# usb-shock-buzzer.net
KiCad netlist of a schematic drawn in EAGLE
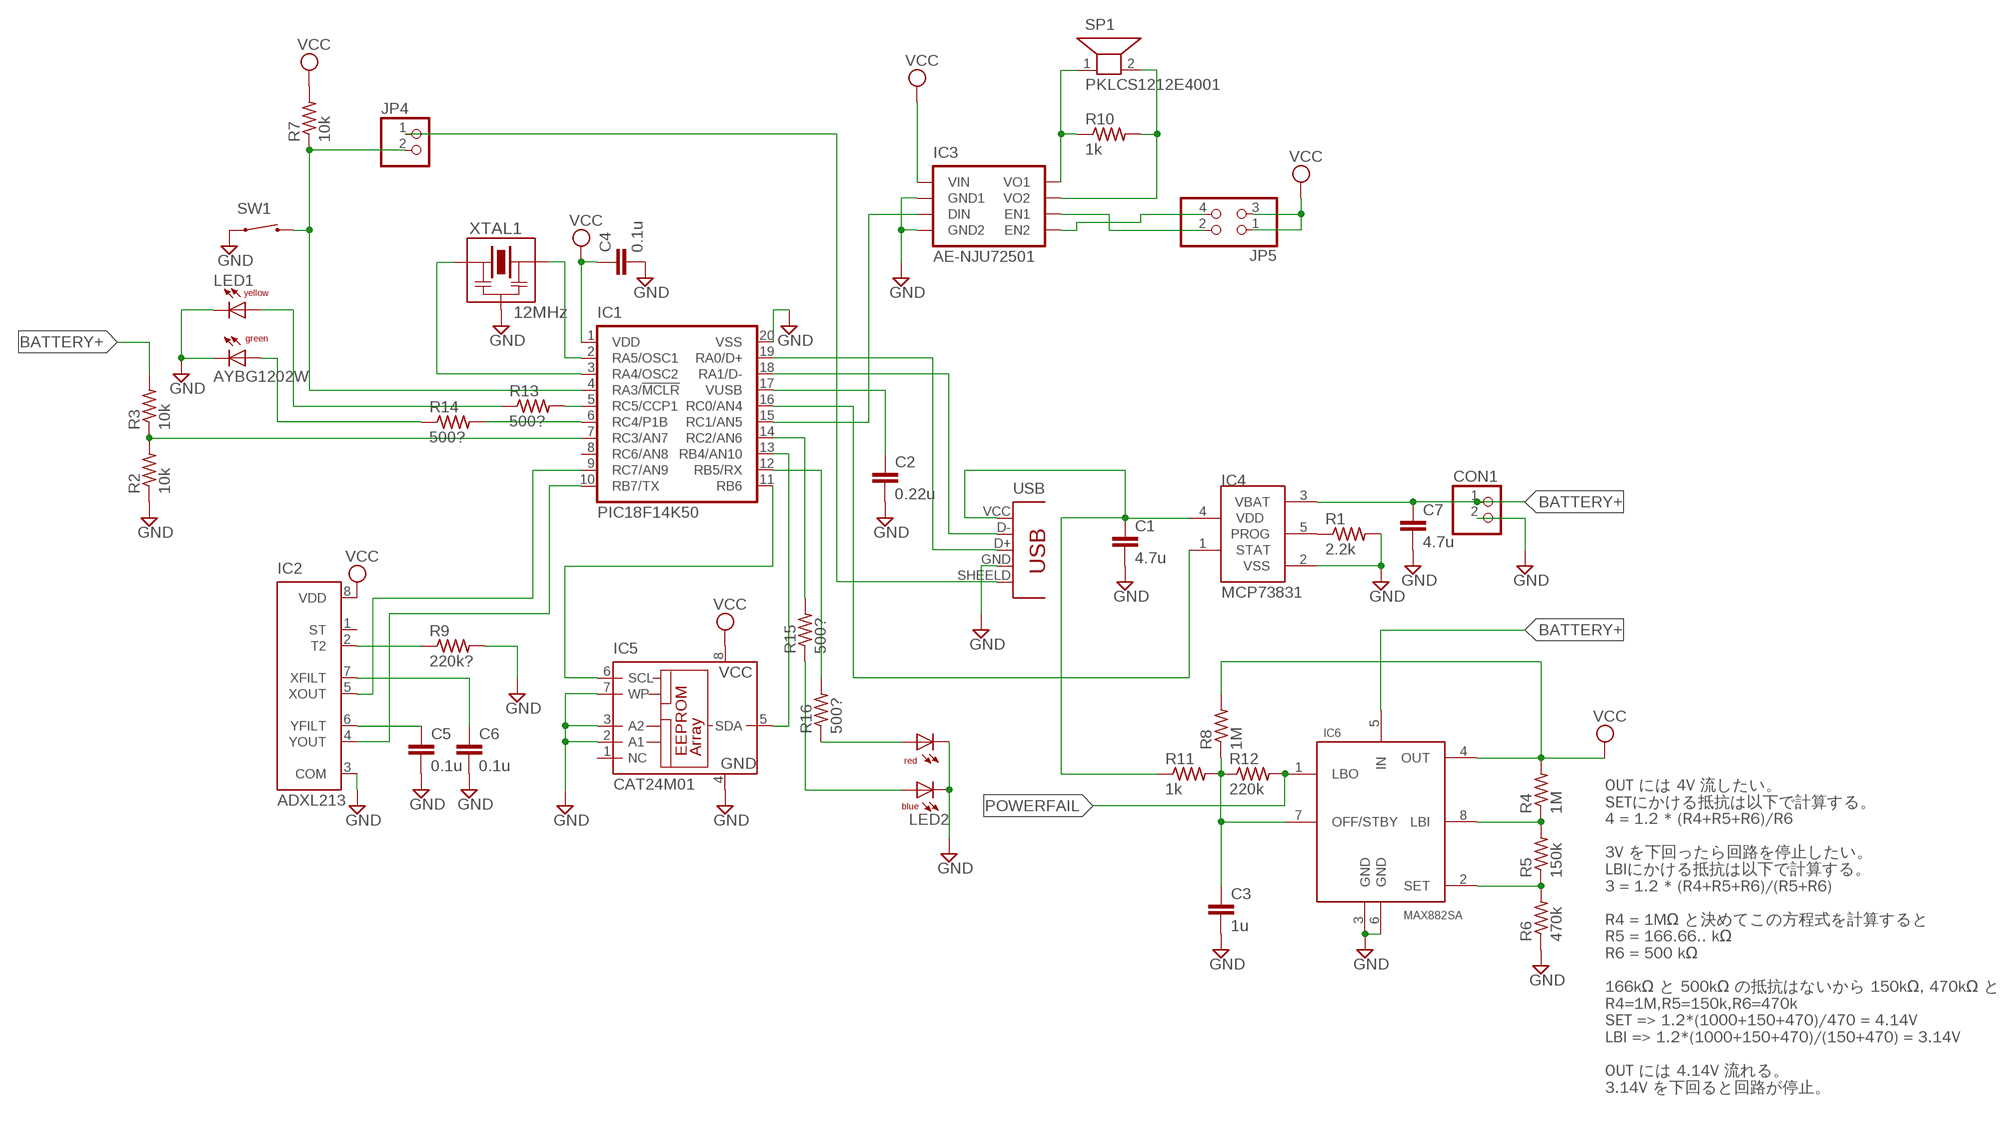
[diagram p0: schematic, sheet 1]

(export (version "E")
  (design (tool "Eeschema 10.0.6"))
  (components
    (comp (ref "C1")
      (value "4.7u")
      (footprint "eagle-import:C0805")
      (libsource (lib "eagle-import") (part "C-EUC0805"))
    )
    (comp (ref "C2")
      (value "0.22u")
      (footprint "eagle-import:C0805")
      (libsource (lib "eagle-import") (part "C-EUC0805"))
    )
    (comp (ref "C3")
      (value "1u")
      (footprint "eagle-import:C0805")
      (libsource (lib "eagle-import") (part "C-EUC0805"))
    )
    (comp (ref "C4")
      (value "0.1u")
      (footprint "eagle-import:C0805")
      (libsource (lib "eagle-import") (part "C-EUC0805"))
    )
    (comp (ref "C5")
      (value "0.1u")
      (footprint "eagle-import:C0805")
      (libsource (lib "eagle-import") (part "C-EUC0805"))
    )
    (comp (ref "C6")
      (value "0.1u")
      (footprint "eagle-import:C0805")
      (libsource (lib "eagle-import") (part "C-EUC0805"))
    )
    (comp (ref "C7")
      (value "4.7u")
      (footprint "eagle-import:C0805")
      (libsource (lib "eagle-import") (part "C-EUC0805"))
    )
    (comp (ref "CON1")
      (value "PH-2PIN")
      (footprint "eagle-import:PH-2PIN")
      (libsource (lib "eagle-import") (part "PH-2PIN"))
    )
    (comp (ref "IC1")
      (value "PIC18F14K50")
      (footprint "eagle-import:SO20")
      (libsource (lib "eagle-import") (part "PIC18F14K50"))
    )
    (comp (ref "IC2")
      (value "ADXL213")
      (footprint "eagle-import:LCC8")
      (libsource (lib "eagle-import") (part "ADXL213"))
    )
    (comp (ref "IC3")
      (value "AE-NJU72501")
      (footprint "eagle-import:AE-NJU72501")
      (libsource (lib "eagle-import") (part "AE-NJU72501"))
    )
    (comp (ref "IC4")
      (value "MCP73831")
      (footprint "eagle-import:SOT23-5L")
      (libsource (lib "eagle-import") (part "MCP73831"))
    )
    (comp (ref "IC5")
      (value "CAT24M01")
      (footprint "eagle-import:SOIC")
      (libsource (lib "eagle-import") (part "CAT24M01"))
    )
    (comp (ref "IC6")
      (value "MAX882SA")
      (footprint "eagle-import:8-SO")
      (libsource (lib "eagle-import") (part "MAX882SA"))
    )
    (comp (ref "JP4")
      (value "PINHD-1X2")
      (footprint "eagle-import:1X02")
      (libsource (lib "eagle-import") (part "PINHD-1X2"))
    )
    (comp (ref "JP5")
      (value "PINHD-2X2")
      (footprint "eagle-import:2X02")
      (libsource (lib "eagle-import") (part "PINHD-2X2"))
    )
    (comp (ref "LED1")
      (value "AYBG1202W")
      (footprint "eagle-import:AYBG1202W")
      (libsource (lib "eagle-import") (part "AYBG1202W"))
    )
    (comp (ref "LED2")
      (value "2COLOR-BR")
      (footprint "eagle-import:SML-02")
      (libsource (lib "eagle-import") (part "2COLOR-BR"))
    )
    (comp (ref "R1")
      (value "2.2k")
      (footprint "eagle-import:M0805")
      (libsource (lib "eagle-import") (part "R-US_M0805"))
    )
    (comp (ref "R2")
      (value "10k")
      (footprint "eagle-import:M0805")
      (libsource (lib "eagle-import") (part "R-US_M0805"))
    )
    (comp (ref "R3")
      (value "10k")
      (footprint "eagle-import:M0805")
      (libsource (lib "eagle-import") (part "R-US_M0805"))
    )
    (comp (ref "R4")
      (value "1M")
      (footprint "eagle-import:R0805")
      (libsource (lib "eagle-import") (part "R-US_R0805"))
    )
    (comp (ref "R5")
      (value "150k")
      (footprint "eagle-import:M0805")
      (libsource (lib "eagle-import") (part "R-US_M0805"))
    )
    (comp (ref "R6")
      (value "470k")
      (footprint "eagle-import:M0805")
      (libsource (lib "eagle-import") (part "R-US_M0805"))
    )
    (comp (ref "R7")
      (value "10k")
      (footprint "eagle-import:M0805")
      (libsource (lib "eagle-import") (part "R-US_M0805"))
    )
    (comp (ref "R8")
      (value "1M")
      (footprint "eagle-import:M0805")
      (libsource (lib "eagle-import") (part "R-US_M0805"))
    )
    (comp (ref "R9")
      (value "220k?")
      (footprint "eagle-import:M0805")
      (libsource (lib "eagle-import") (part "R-US_M0805"))
    )
    (comp (ref "R10")
      (value "1k")
      (footprint "eagle-import:M1206")
      (libsource (lib "eagle-import") (part "R-US_M1206"))
    )
    (comp (ref "R11")
      (value "1k")
      (footprint "eagle-import:M0805")
      (libsource (lib "eagle-import") (part "R-US_M0805"))
    )
    (comp (ref "R12")
      (value "220k")
      (footprint "eagle-import:M0805")
      (libsource (lib "eagle-import") (part "R-US_M0805"))
    )
    (comp (ref "R13")
      (value "500?")
      (footprint "eagle-import:M0805")
      (libsource (lib "eagle-import") (part "R-US_M0805"))
    )
    (comp (ref "R14")
      (value "500?")
      (footprint "eagle-import:M0805")
      (libsource (lib "eagle-import") (part "R-US_M0805"))
    )
    (comp (ref "R15")
      (value "500?")
      (footprint "eagle-import:M0805")
      (libsource (lib "eagle-import") (part "R-US_M0805"))
    )
    (comp (ref "R16")
      (value "500?")
      (footprint "eagle-import:M0805")
      (libsource (lib "eagle-import") (part "R-US_M0805"))
    )
    (comp (ref "SP1")
      (value "PKLCS1212E4001")
      (footprint "eagle-import:PKLCS1212E4001")
      (libsource (lib "eagle-import") (part "PKLCS1212E4001"))
    )
    (comp (ref "SW1")
      (value "TVBP06")
      (footprint "eagle-import:TVBP06")
      (libsource (lib "eagle-import") (part "TVBP06"))
    )
    (comp (ref "USB")
      (value "TYPE-A+SHILED")
      (footprint "eagle-import:TYPE-A")
      (libsource (lib "eagle-import") (part "TYPE-A+SHILED"))
    )
    (comp (ref "XTAL1")
      (value "12MHz")
      (footprint "eagle-import:CSTCE")
      (libsource (lib "eagle-import") (part "CSTCE12M0G15L"))
    )
  )
  (nets
    (net (code "1") (name "BATTERY+") (class "Default")
      (node (ref "C7") (pin "1") (pinfunction "1_1") (pintype "passive"))
      (node (ref "CON1") (pin "1") (pinfunction "1_1") (pintype "passive"))
      (node (ref "IC4") (pin "3") (pinfunction "VBAT_3") (pintype "bidirectional"))
      (node (ref "IC6") (pin "5") (pinfunction "IN_5") (pintype "power_in"))
      (node (ref "R3") (pin "2") (pinfunction "2_2") (pintype "passive"))
    )
    (net (code "2") (name "GND") (class "Default")
      (node (ref "C1") (pin "2") (pinfunction "2_2") (pintype "passive"))
      (node (ref "C2") (pin "2") (pinfunction "2_2") (pintype "passive"))
      (node (ref "C3") (pin "2") (pinfunction "2_2") (pintype "passive"))
      (node (ref "C4") (pin "2") (pinfunction "2_2") (pintype "passive"))
      (node (ref "C5") (pin "2") (pinfunction "2_2") (pintype "passive"))
      (node (ref "C6") (pin "2") (pinfunction "2_2") (pintype "passive"))
      (node (ref "C7") (pin "2") (pinfunction "2_2") (pintype "passive"))
      (node (ref "CON1") (pin "2") (pinfunction "2_2") (pintype "passive"))
      (node (ref "IC1") (pin "20") (pinfunction "VSS_20") (pintype "power_in"))
      (node (ref "IC2") (pin "3") (pinfunction "COM_3") (pintype "input"))
      (node (ref "IC3") (pin "2") (pinfunction "GND1_2") (pintype "power_in"))
      (node (ref "IC3") (pin "4") (pinfunction "GND2_4") (pintype "power_in"))
      (node (ref "IC4") (pin "2") (pinfunction "VSS_2") (pintype "bidirectional"))
      (node (ref "IC5") (pin "2") (pinfunction "A1_2") (pintype "input"))
      (node (ref "IC5") (pin "3") (pinfunction "A2_3") (pintype "input"))
      (node (ref "IC5") (pin "4") (pinfunction "GND_4") (pintype "power_in"))
      (node (ref "IC5") (pin "7") (pinfunction "WP_7") (pintype "input"))
      (node (ref "IC6") (pin "3") (pinfunction "GND_3") (pintype "power_in"))
      (node (ref "IC6") (pin "6") (pinfunction "GND_6") (pintype "power_in"))
      (node (ref "LED1") (pin "2") (pinfunction "CC1_2") (pintype "passive"))
      (node (ref "LED1") (pin "4") (pinfunction "CC2_4") (pintype "passive"))
      (node (ref "LED2") (pin "1") (pinfunction "CC1_1") (pintype "passive"))
      (node (ref "LED2") (pin "3") (pinfunction "CC2_3") (pintype "passive"))
      (node (ref "R1") (pin "2") (pinfunction "2_2") (pintype "passive"))
      (node (ref "R2") (pin "1") (pinfunction "1_1") (pintype "passive"))
      (node (ref "R6") (pin "1") (pinfunction "1_1") (pintype "passive"))
      (node (ref "R9") (pin "2") (pinfunction "2_2") (pintype "passive"))
      (node (ref "SW1") (pin "1") (pinfunction "1_1") (pintype "passive"))
      (node (ref "USB") (pin "GND") (pinfunction "4_GND") (pintype "power_in"))
      (node (ref "XTAL1") (pin "2") (pinfunction "GND_2") (pintype "bidirectional"))
    )
    (net (code "3") (name "Net-(IC1-RA0{slash}D+)") (class "Default")
      (node (ref "IC1") (pin "19") (pinfunction "RA0/D+_19") (pintype "bidirectional"))
      (node (ref "USB") (pin "D+") (pinfunction "3_D+") (pintype "passive"))
    )
    (net (code "4") (name "Net-(IC1-RA1{slash}D-)") (class "Default")
      (node (ref "IC1") (pin "18") (pinfunction "RA1/D-_18") (pintype "bidirectional"))
      (node (ref "USB") (pin "D-") (pinfunction "2_D-") (pintype "passive"))
    )
    (net (code "5") (name "Net-(IC1-RA3{slash}~{MCLR})") (class "Default")
      (node (ref "IC1") (pin "4") (pinfunction "RA3/~{MCLR}_4") (pintype "bidirectional"))
      (node (ref "JP4") (pin "2") (pinfunction "2_2") (pintype "passive"))
      (node (ref "R7") (pin "1") (pinfunction "1_1") (pintype "passive"))
      (node (ref "SW1") (pin "2") (pinfunction "2_2") (pintype "passive"))
    )
    (net (code "6") (name "Net-(IC1-RA4{slash}OSC2)") (class "Default")
      (node (ref "IC1") (pin "3") (pinfunction "RA4/OSC2_3") (pintype "bidirectional"))
      (node (ref "XTAL1") (pin "1") (pinfunction "LFT_1") (pintype "bidirectional"))
    )
    (net (code "7") (name "Net-(IC1-RA5{slash}OSC1)") (class "Default")
      (node (ref "IC1") (pin "2") (pinfunction "RA5/OSC1_2") (pintype "bidirectional"))
      (node (ref "XTAL1") (pin "3") (pinfunction "RIT_3") (pintype "bidirectional"))
    )
    (net (code "8") (name "Net-(IC1-RB4{slash}AN10)") (class "Default")
      (node (ref "IC1") (pin "13") (pinfunction "RB4/AN10_13") (pintype "bidirectional"))
      (node (ref "IC5") (pin "5") (pinfunction "SDA_5") (pintype "bidirectional"))
    )
    (net (code "9") (name "Net-(IC1-RB5{slash}RX)") (class "Default")
      (node (ref "IC1") (pin "12") (pinfunction "RB5/RX_12") (pintype "bidirectional"))
      (node (ref "R16") (pin "2") (pinfunction "2_2") (pintype "passive"))
    )
    (net (code "10") (name "Net-(IC1-RB6)") (class "Default")
      (node (ref "IC1") (pin "11") (pinfunction "RB6_11") (pintype "bidirectional"))
      (node (ref "IC5") (pin "6") (pinfunction "SCL_6") (pintype "input"))
    )
    (net (code "11") (name "Net-(IC1-RB7{slash}TX)") (class "Default")
      (node (ref "IC1") (pin "10") (pinfunction "RB7/TX_10") (pintype "bidirectional"))
      (node (ref "IC2") (pin "4") (pinfunction "YOUT_4") (pintype "input"))
    )
    (net (code "12") (name "Net-(IC1-RC0{slash}AN4)") (class "Default")
      (node (ref "IC1") (pin "16") (pinfunction "RC0/AN4_16") (pintype "bidirectional"))
      (node (ref "IC4") (pin "1") (pinfunction "STAT_1") (pintype "bidirectional"))
    )
    (net (code "13") (name "Net-(IC1-RC1{slash}AN5)") (class "Default")
      (node (ref "IC1") (pin "15") (pinfunction "RC1/AN5_15") (pintype "bidirectional"))
      (node (ref "IC3") (pin "3") (pinfunction "DIN_3") (pintype "bidirectional"))
    )
    (net (code "14") (name "Net-(IC1-RC2{slash}AN6)") (class "Default")
      (node (ref "IC1") (pin "14") (pinfunction "RC2/AN6_14") (pintype "bidirectional"))
      (node (ref "R15") (pin "2") (pinfunction "2_2") (pintype "passive"))
    )
    (net (code "15") (name "Net-(IC1-RC3{slash}AN7)") (class "Default")
      (node (ref "IC1") (pin "7") (pinfunction "RC3/AN7_7") (pintype "bidirectional"))
      (node (ref "R2") (pin "2") (pinfunction "2_2") (pintype "passive"))
      (node (ref "R3") (pin "1") (pinfunction "1_1") (pintype "passive"))
    )
    (net (code "16") (name "Net-(IC1-RC4{slash}P1B)") (class "Default")
      (node (ref "IC1") (pin "6") (pinfunction "RC4/P1B_6") (pintype "bidirectional"))
      (node (ref "R14") (pin "2") (pinfunction "2_2") (pintype "passive"))
    )
    (net (code "17") (name "Net-(IC1-RC5{slash}CCP1)") (class "Default")
      (node (ref "IC1") (pin "5") (pinfunction "RC5/CCP1_5") (pintype "bidirectional"))
      (node (ref "R13") (pin "2") (pinfunction "2_2") (pintype "passive"))
    )
    (net (code "18") (name "Net-(IC1-RC7{slash}AN9)") (class "Default")
      (node (ref "IC1") (pin "9") (pinfunction "RC7/AN9_9") (pintype "bidirectional"))
      (node (ref "IC2") (pin "5") (pinfunction "XOUT_5") (pintype "input"))
    )
    (net (code "19") (name "Net-(IC1-VUSB)") (class "Default")
      (node (ref "C2") (pin "1") (pinfunction "1_1") (pintype "passive"))
      (node (ref "IC1") (pin "17") (pinfunction "VUSB_17") (pintype "bidirectional"))
    )
    (net (code "20") (name "Net-(IC2-T2)") (class "Default")
      (node (ref "IC2") (pin "2") (pinfunction "T2_2") (pintype "input"))
      (node (ref "R9") (pin "1") (pinfunction "1_1") (pintype "passive"))
    )
    (net (code "21") (name "Net-(IC2-XFILT)") (class "Default")
      (node (ref "C6") (pin "1") (pinfunction "1_1") (pintype "passive"))
      (node (ref "IC2") (pin "7") (pinfunction "XFILT_7") (pintype "input"))
    )
    (net (code "22") (name "Net-(IC2-YFILT)") (class "Default")
      (node (ref "C5") (pin "1") (pinfunction "1_1") (pintype "passive"))
      (node (ref "IC2") (pin "6") (pinfunction "YFILT_6") (pintype "input"))
    )
    (net (code "23") (name "Net-(IC3-EN1)") (class "Default")
      (node (ref "IC3") (pin "6") (pinfunction "EN1_6") (pintype "bidirectional"))
      (node (ref "JP5") (pin "2") (pinfunction "2_2") (pintype "passive"))
    )
    (net (code "24") (name "Net-(IC3-EN2)") (class "Default")
      (node (ref "IC3") (pin "5") (pinfunction "EN2_5") (pintype "power_in"))
      (node (ref "JP5") (pin "4") (pinfunction "4_4") (pintype "passive"))
    )
    (net (code "25") (name "Net-(IC3-VO1)") (class "Default")
      (node (ref "IC3") (pin "8") (pinfunction "VO1_8") (pintype "bidirectional"))
      (node (ref "R10") (pin "1") (pinfunction "1_1") (pintype "passive"))
      (node (ref "SP1") (pin "1") (pinfunction "1_1") (pintype "passive"))
    )
    (net (code "26") (name "Net-(IC3-VO2)") (class "Default")
      (node (ref "IC3") (pin "7") (pinfunction "VO2_7") (pintype "bidirectional"))
      (node (ref "R10") (pin "2") (pinfunction "2_2") (pintype "passive"))
      (node (ref "SP1") (pin "2") (pinfunction "2_2") (pintype "passive"))
    )
    (net (code "27") (name "Net-(IC4-PROG)") (class "Default")
      (node (ref "IC4") (pin "5") (pinfunction "PROG_5") (pintype "bidirectional"))
      (node (ref "R1") (pin "1") (pinfunction "1_1") (pintype "passive"))
    )
    (net (code "28") (name "Net-(IC4-VDD)") (class "Default")
      (node (ref "C1") (pin "1") (pinfunction "1_1") (pintype "passive"))
      (node (ref "IC4") (pin "4") (pinfunction "VDD_4") (pintype "bidirectional"))
      (node (ref "R11") (pin "1") (pinfunction "1_1") (pintype "passive"))
      (node (ref "USB") (pin "VCC") (pinfunction "1_VCC") (pintype "power_in"))
    )
    (net (code "29") (name "Net-(IC6-LBI)") (class "Default")
      (node (ref "IC6") (pin "8") (pinfunction "LBI_8") (pintype "passive"))
      (node (ref "R4") (pin "1") (pinfunction "1_1") (pintype "passive"))
      (node (ref "R5") (pin "2") (pinfunction "2_2") (pintype "passive"))
    )
    (net (code "30") (name "Net-(IC6-OFF{slash}STBY)") (class "Default")
      (node (ref "C3") (pin "1") (pinfunction "1_1") (pintype "passive"))
      (node (ref "IC6") (pin "7") (pinfunction "OFF/STBY_7") (pintype "passive"))
      (node (ref "R11") (pin "2") (pinfunction "2_2") (pintype "passive"))
      (node (ref "R12") (pin "1") (pinfunction "1_1") (pintype "passive"))
      (node (ref "R8") (pin "1") (pinfunction "1_1") (pintype "passive"))
    )
    (net (code "31") (name "Net-(IC6-SET)") (class "Default")
      (node (ref "IC6") (pin "2") (pinfunction "SET_2") (pintype "passive"))
      (node (ref "R5") (pin "1") (pinfunction "1_1") (pintype "passive"))
      (node (ref "R6") (pin "2") (pinfunction "2_2") (pintype "passive"))
    )
    (net (code "32") (name "Net-(LED1-A1)") (class "Default")
      (node (ref "LED1") (pin "1") (pinfunction "A1_1") (pintype "passive"))
      (node (ref "R13") (pin "1") (pinfunction "1_1") (pintype "passive"))
    )
    (net (code "33") (name "Net-(LED1-A2)") (class "Default")
      (node (ref "LED1") (pin "3") (pinfunction "A2_3") (pintype "passive"))
      (node (ref "R14") (pin "1") (pinfunction "1_1") (pintype "passive"))
    )
    (net (code "34") (name "Net-(LED2-AB)") (class "Default")
      (node (ref "LED2") (pin "2") (pinfunction "AB_2") (pintype "passive"))
      (node (ref "R15") (pin "1") (pinfunction "1_1") (pintype "passive"))
    )
    (net (code "35") (name "Net-(LED2-AR)") (class "Default")
      (node (ref "LED2") (pin "4") (pinfunction "AR_4") (pintype "passive"))
      (node (ref "R16") (pin "1") (pinfunction "1_1") (pintype "passive"))
    )
    (net (code "36") (name "Net-(USB-5)") (class "Default")
      (node (ref "JP4") (pin "1") (pinfunction "1_1") (pintype "passive"))
      (node (ref "USB") (pin "SHEELD") (pinfunction "5_SHEELD") (pintype "passive"))
    )
    (net (code "37") (name "POWERFAIL") (class "Default")
      (node (ref "IC6") (pin "1") (pinfunction "LBO_1") (pintype "open_collector"))
      (node (ref "R12") (pin "2") (pinfunction "2_2") (pintype "passive"))
    )
    (net (code "38") (name "VCC") (class "Default")
      (node (ref "C4") (pin "1") (pinfunction "1_1") (pintype "passive"))
      (node (ref "IC1") (pin "1") (pinfunction "VDD_1") (pintype "power_in"))
      (node (ref "IC2") (pin "8") (pinfunction "VDD_8") (pintype "input"))
      (node (ref "IC3") (pin "1") (pinfunction "VIN_1") (pintype "power_in"))
      (node (ref "IC5") (pin "8") (pinfunction "VCC_8") (pintype "power_in"))
      (node (ref "IC6") (pin "4") (pinfunction "OUT_4") (pintype "power_in"))
      (node (ref "JP5") (pin "1") (pinfunction "1_1") (pintype "passive"))
      (node (ref "JP5") (pin "3") (pinfunction "3_3") (pintype "passive"))
      (node (ref "R4") (pin "2") (pinfunction "2_2") (pintype "passive"))
      (node (ref "R7") (pin "2") (pinfunction "2_2") (pintype "passive"))
      (node (ref "R8") (pin "2") (pinfunction "2_2") (pintype "passive"))
    )
    (net (code "39") (name "unconnected-(IC1-RC6{slash}AN8-Pad8)") (class "Default")
      (node (ref "IC1") (pin "8") (pinfunction "RC6/AN8_8") (pintype "bidirectional"))
    )
    (net (code "40") (name "unconnected-(IC2-ST-Pad1)") (class "Default")
      (node (ref "IC2") (pin "1") (pinfunction "ST_1") (pintype "input"))
    )
    (net (code "41") (name "unconnected-(IC5-NC-Pad1)") (class "Default")
      (node (ref "IC5") (pin "1") (pinfunction "NC_1") (pintype "input"))
    )
  )
)
